# Sheet1.net
KiCad netlist of a schematic drawn in Altium Designer
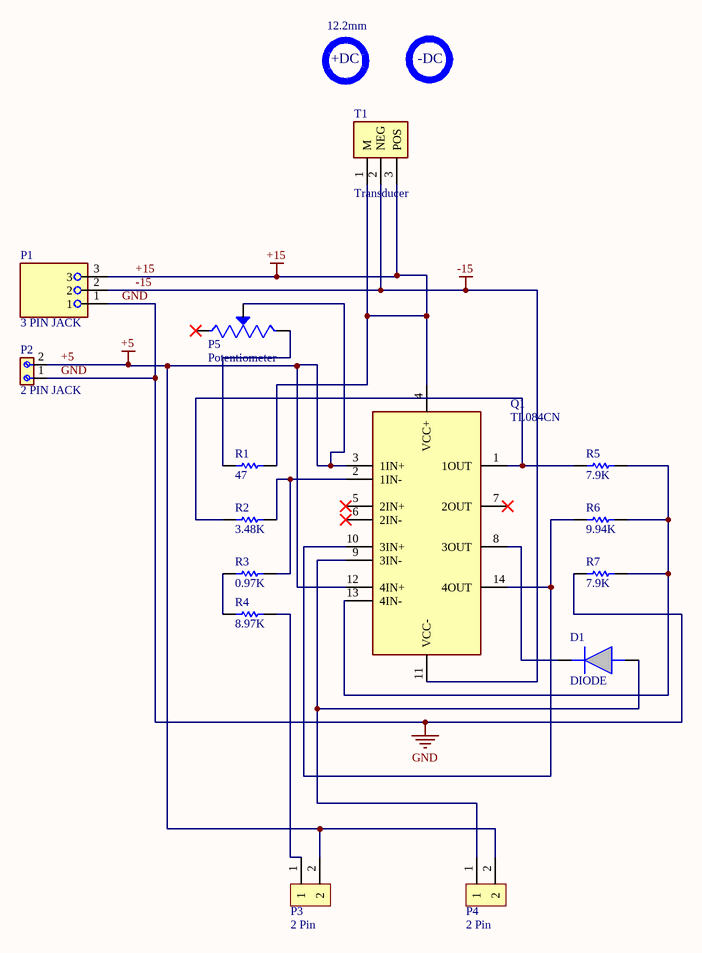
[diagram p0: Sheet1.SchDoc]

(export (version "E")
  (design (tool "Eeschema 10.0.6"))
  (components
    (comp (ref "D1")
      (value "DIODE")
      (footprint "Diode")
      (description "1N4007S")
      (libsource (lib "Schlib1") (part "DIODE"))
    )
    (comp (ref "P1")
      (value "3 PIN JACK")
      (footprint "3 PIN JACK")
      (libsource (lib "Schlib1") (part "3 PIN JACK"))
    )
    (comp (ref "P2")
      (value "2 PIN JACK")
      (footprint "2 PIN JACK")
      (libsource (lib "Schlib1") (part "2 PIN JACK"))
    )
    (comp (ref "P3")
      (value "2 Pin")
      (footprint "2 PIN")
      (description "22272021")
      (libsource (lib "Schlib1") (part "2 Pin"))
    )
    (comp (ref "P4")
      (value "2 Pin")
      (footprint "2 PIN")
      (description "22272021")
      (libsource (lib "Schlib1") (part "2 Pin"))
    )
    (comp (ref "P5")
      (value "Potentiometer")
      (footprint "Potentiometer")
      (libsource (lib "Schlib1") (part "Potentiometer"))
    )
    (comp (ref "Q1") (value "TL084CN") (footprint "TL084CN") (libsource (lib "Schlib1") (part "TL084CN")))
    (comp (ref "R1")
      (value "47")
      (footprint "47")
      (description "MFR-25FRF52-47R")
      (libsource (lib "Schlib1") (part "47"))
    )
    (comp (ref "R2")
      (value "3.48K")
      (footprint "3.48K")
      (description "MFR-25FBF52-3K48")
      (libsource (lib "Schlib1") (part "3.48K"))
    )
    (comp (ref "R3")
      (value "0.97K")
      (footprint "0.97K")
      (description "MFR-25FRF52-976R")
      (libsource (lib "Schlib1") (part "0.97K"))
    )
    (comp (ref "R4")
      (value "8.97K")
      (footprint "8.97K")
      (description "MFR-25FBF52-8K87")
      (libsource (lib "Schlib1") (part "8.97K"))
    )
    (comp (ref "R5")
      (value "7.9K")
      (footprint "7.90K")
      (description "MFR-25FBF52-7K87")
      (libsource (lib "Schlib1") (part "7.9K"))
    )
    (comp (ref "R6")
      (value "9.94K")
      (footprint "9.94K")
      (description "MFR-25FTE52-9K76")
      (libsource (lib "Schlib1") (part "9.94K"))
    )
    (comp (ref "R7")
      (value "7.9K")
      (footprint "7.90K")
      (description "MFR-25FBF52-7K87")
      (libsource (lib "Schlib1") (part "7.9K"))
    )
    (comp (ref "T1")
      (value "Transducer")
      (footprint "Transducer")
      (description "LA55-P")
      (libsource (lib "Schlib1") (part "Transducer"))
    )
  )
  (nets
    (net (code "1") (name "+5") (class "Default")
      (node (ref "P2") (pin "2") (pinfunction "2_2") (pintype "passive"))
      (node (ref "P3") (pin "2") (pinfunction "2_2") (pintype "passive"))
      (node (ref "P4") (pin "2") (pinfunction "2_2") (pintype "passive"))
      (node (ref "P5") (pin "2") (pinfunction "WIPER_2") (pintype "passive"))
      (node (ref "Q1") (pin "12") (pinfunction "4IN+_12") (pintype "passive"))
      (node (ref "Q1") (pin "3") (pinfunction "1IN+_3") (pintype "passive"))
    )
    (net (code "2") (name "+15") (class "Default")
      (node (ref "P1") (pin "3") (pinfunction "3_3") (pintype "passive"))
      (node (ref "Q1") (pin "4") (pinfunction "VCC+_4") (pintype "power_in"))
      (node (ref "R1") (pin "2") (pinfunction "2_2") (pintype "passive"))
      (node (ref "T1") (pin "1") (pinfunction "M_1") (pintype "power_in"))
      (node (ref "T1") (pin "3") (pinfunction "POS_3") (pintype "power_in"))
    )
    (net (code "3") (name "-15") (class "Default")
      (node (ref "P1") (pin "2") (pinfunction "2_2") (pintype "passive"))
      (node (ref "Q1") (pin "11") (pinfunction "VCC-_11") (pintype "power_in"))
      (node (ref "T1") (pin "2") (pinfunction "NEG_2") (pintype "power_in"))
    )
    (net (code "4") (name "GND") (class "Default")
      (node (ref "P1") (pin "1") (pinfunction "1_1") (pintype "passive"))
      (node (ref "P2") (pin "1") (pinfunction "1_1") (pintype "passive"))
      (node (ref "R7") (pin "1") (pinfunction "1_1") (pintype "passive"))
    )
    (net (code "5") (name "Net-(D1-A)") (class "Default")
      (node (ref "D1") (pin "2") (pinfunction "A_2") (pintype "passive"))
      (node (ref "P4") (pin "1") (pinfunction "1_1") (pintype "passive"))
      (node (ref "Q1") (pin "9") (pinfunction "3IN-_9") (pintype "passive"))
    )
    (net (code "6") (name "Net-(D1-K)") (class "Default")
      (node (ref "D1") (pin "1") (pinfunction "K_1") (pintype "passive"))
      (node (ref "Q1") (pin "8") (pinfunction "3OUT_8") (pintype "passive"))
    )
    (net (code "7") (name "Net-(P3-Pad1)") (class "Default")
      (node (ref "P3") (pin "1") (pinfunction "1_1") (pintype "passive"))
      (node (ref "R4") (pin "2") (pinfunction "2_2") (pintype "passive"))
    )
    (net (code "8") (name "Net-(P5-CW)") (class "Default")
      (node (ref "P5") (pin "3") (pinfunction "CW_3") (pintype "passive"))
      (node (ref "R1") (pin "1") (pinfunction "1_1") (pintype "passive"))
    )
    (net (code "9") (name "Net-(Q1-1IN-)") (class "Default")
      (node (ref "Q1") (pin "2") (pinfunction "1IN-_2") (pintype "passive"))
      (node (ref "R2") (pin "2") (pinfunction "2_2") (pintype "passive"))
      (node (ref "R3") (pin "2") (pinfunction "2_2") (pintype "passive"))
    )
    (net (code "10") (name "Net-(Q1-1OUT)") (class "Default")
      (node (ref "Q1") (pin "1") (pinfunction "1OUT_1") (pintype "passive"))
      (node (ref "R2") (pin "1") (pinfunction "1_1") (pintype "passive"))
      (node (ref "R5") (pin "1") (pinfunction "1_1") (pintype "passive"))
    )
    (net (code "11") (name "Net-(Q1-3IN+)") (class "Default")
      (node (ref "Q1") (pin "10") (pinfunction "3IN+_10") (pintype "passive"))
      (node (ref "Q1") (pin "14") (pinfunction "4OUT_14") (pintype "passive"))
      (node (ref "R6") (pin "1") (pinfunction "1_1") (pintype "passive"))
    )
    (net (code "12") (name "Net-(Q1-4IN-)") (class "Default")
      (node (ref "Q1") (pin "13") (pinfunction "4IN-_13") (pintype "passive"))
      (node (ref "R5") (pin "2") (pinfunction "2_2") (pintype "passive"))
      (node (ref "R6") (pin "2") (pinfunction "2_2") (pintype "passive"))
      (node (ref "R7") (pin "2") (pinfunction "2_2") (pintype "passive"))
    )
    (net (code "13") (name "Net-(R3-Pad1)") (class "Default")
      (node (ref "R3") (pin "1") (pinfunction "1_1") (pintype "passive"))
      (node (ref "R4") (pin "1") (pinfunction "1_1") (pintype "passive"))
    )
    (net (code "14") (name "unconnected-(P5-CCW-Pad1)") (class "Default")
      (node (ref "P5") (pin "1") (pinfunction "CCW_1") (pintype "passive+no_connect"))
    )
    (net (code "15") (name "unconnected-(Q1-2IN+-Pad5)") (class "Default")
      (node (ref "Q1") (pin "5") (pinfunction "2IN+_5") (pintype "passive+no_connect"))
    )
    (net (code "16") (name "unconnected-(Q1-2IN--Pad6)") (class "Default")
      (node (ref "Q1") (pin "6") (pinfunction "2IN-_6") (pintype "passive+no_connect"))
    )
    (net (code "17") (name "unconnected-(Q1-2OUT-Pad7)") (class "Default")
      (node (ref "Q1") (pin "7") (pinfunction "2OUT_7") (pintype "passive+no_connect"))
    )
  )
)
